# 2_classyTKL_SI_matrix.net
KiCad netlist of a schematic drawn in Altium Designer
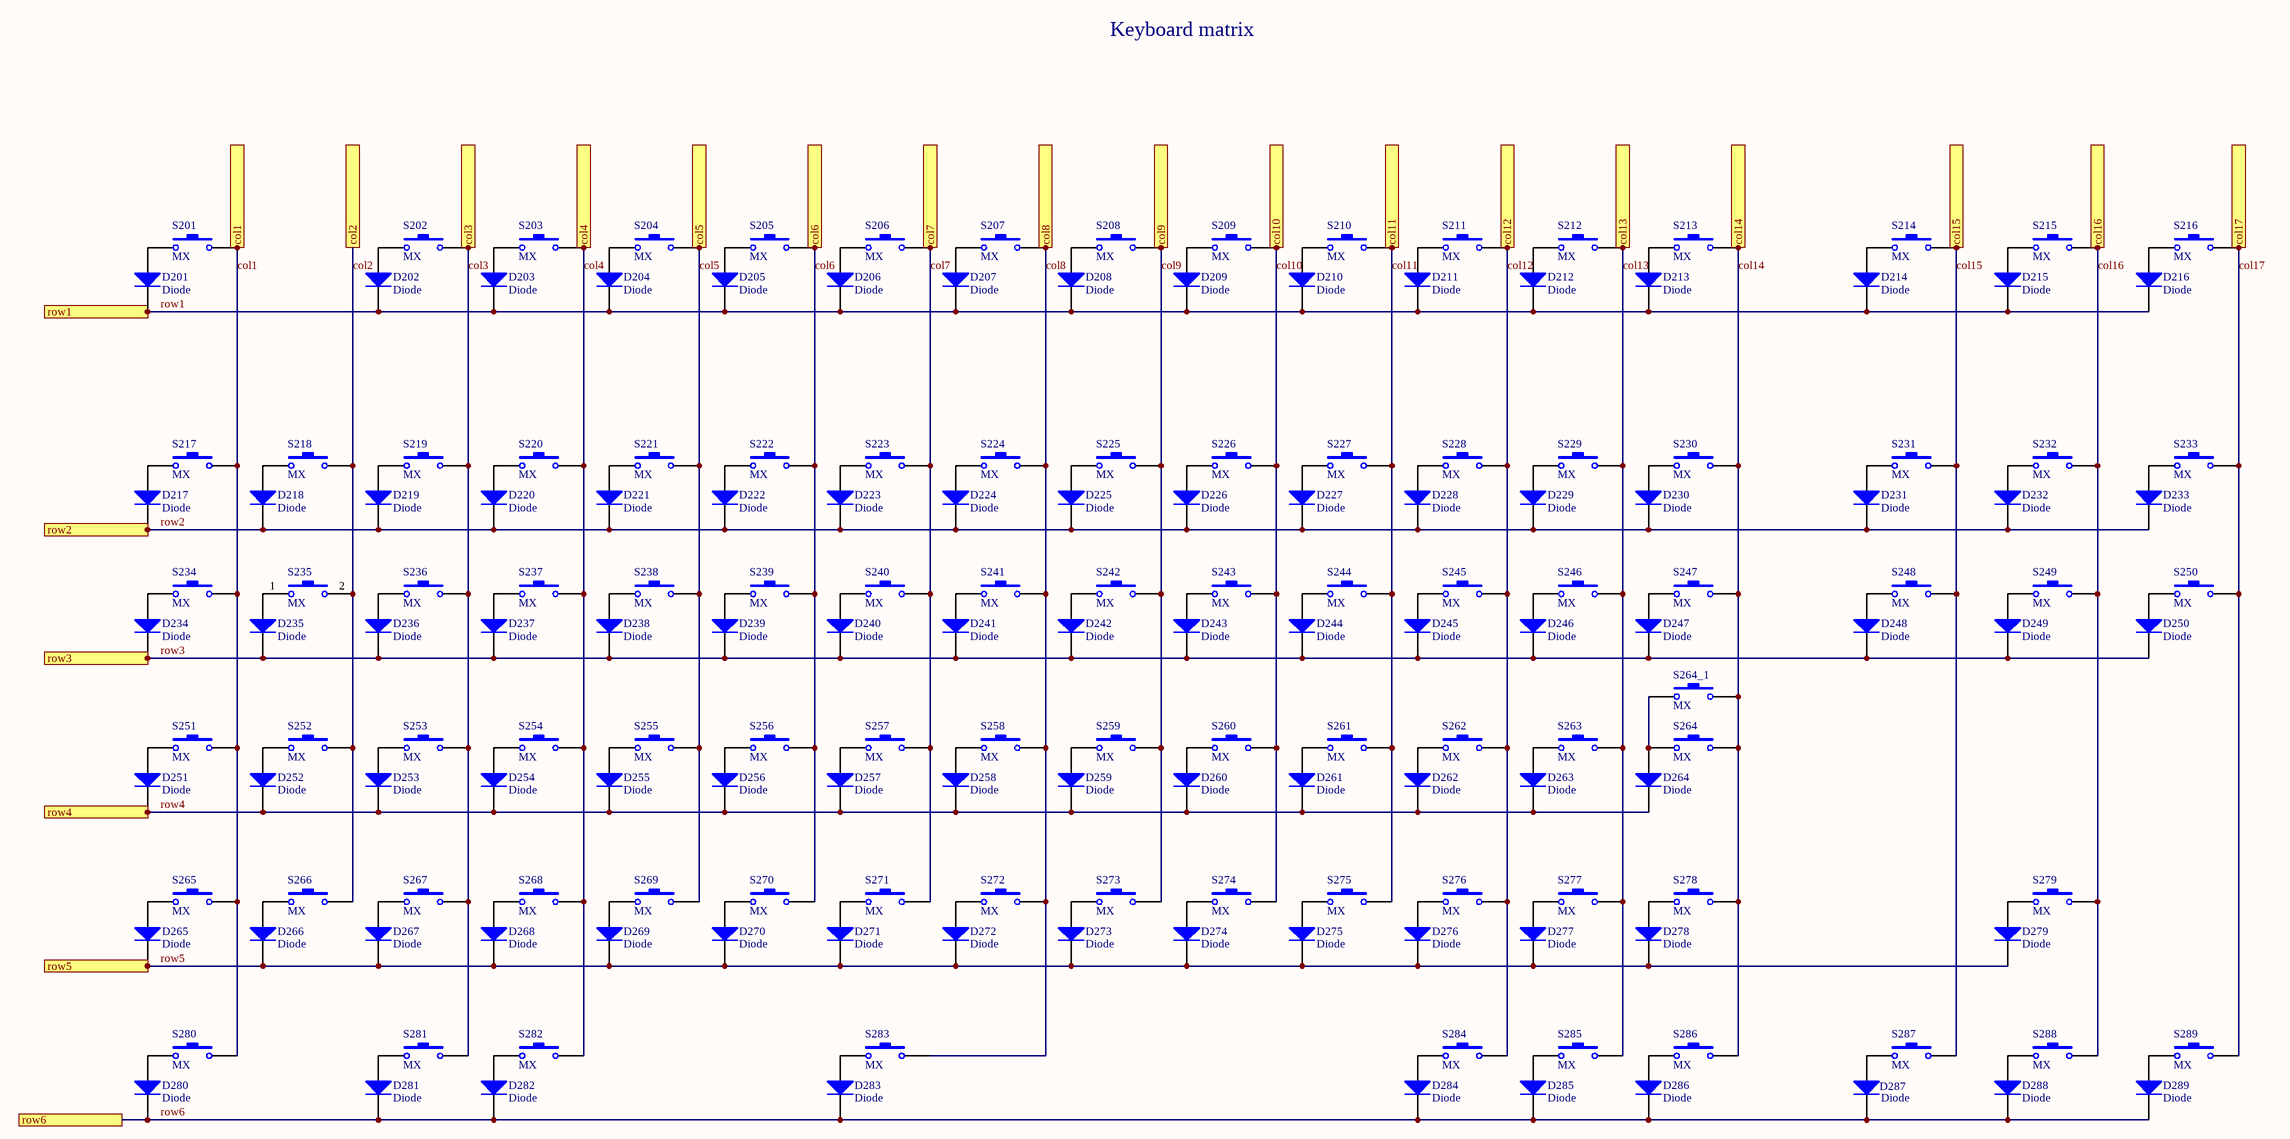
[diagram p0: 2_classyTKL_SI_matrix.SchDoc]

(export (version "E")
  (design (tool "Eeschema 10.0.6"))
  (components
    (comp (ref "D201")
      (value "Diode")
      (footprint "SOD-123")
      (description "Default Diode")
      (fields (field (name "LCSC PART #") "C81598") (field (name "MRF.PART") "1N4148W"))
      (libsource (lib "Miscellaneous Devices") (part "Diode"))
    )
    (comp (ref "D202")
      (value "Diode")
      (footprint "SOD-123")
      (description "Default Diode")
      (fields (field (name "LCSC PART #") "C81598") (field (name "MRF.PART") "1N4148W"))
      (libsource (lib "Miscellaneous Devices") (part "Diode"))
    )
    (comp (ref "D203")
      (value "Diode")
      (footprint "SOD-123")
      (description "Default Diode")
      (fields (field (name "LCSC PART #") "C81598") (field (name "MRF.PART") "1N4148W"))
      (libsource (lib "Miscellaneous Devices") (part "Diode"))
    )
    (comp (ref "D204")
      (value "Diode")
      (footprint "SOD-123")
      (description "Default Diode")
      (fields (field (name "LCSC PART #") "C81598") (field (name "MRF.PART") "1N4148W"))
      (libsource (lib "Miscellaneous Devices") (part "Diode"))
    )
    (comp (ref "D205")
      (value "Diode")
      (footprint "SOD-123")
      (description "Default Diode")
      (fields (field (name "LCSC PART #") "C81598") (field (name "MRF.PART") "1N4148W"))
      (libsource (lib "Miscellaneous Devices") (part "Diode"))
    )
    (comp (ref "D206")
      (value "Diode")
      (footprint "SOD-123")
      (description "Default Diode")
      (fields (field (name "LCSC PART #") "C81598") (field (name "MRF.PART") "1N4148W"))
      (libsource (lib "Miscellaneous Devices") (part "Diode"))
    )
    (comp (ref "D207")
      (value "Diode")
      (footprint "SOD-123")
      (description "Default Diode")
      (fields (field (name "LCSC PART #") "C81598") (field (name "MRF.PART") "1N4148W"))
      (libsource (lib "Miscellaneous Devices") (part "Diode"))
    )
    (comp (ref "D208")
      (value "Diode")
      (footprint "SOD-123")
      (description "Default Diode")
      (fields (field (name "LCSC PART #") "C81598") (field (name "MRF.PART") "1N4148W"))
      (libsource (lib "Miscellaneous Devices") (part "Diode"))
    )
    (comp (ref "D209")
      (value "Diode")
      (footprint "SOD-123")
      (description "Default Diode")
      (fields (field (name "LCSC PART #") "C81598") (field (name "MRF.PART") "1N4148W"))
      (libsource (lib "Miscellaneous Devices") (part "Diode"))
    )
    (comp (ref "D210")
      (value "Diode")
      (footprint "SOD-123")
      (description "Default Diode")
      (fields (field (name "LCSC PART #") "C81598") (field (name "MRF.PART") "1N4148W"))
      (libsource (lib "Miscellaneous Devices") (part "Diode"))
    )
    (comp (ref "D211")
      (value "Diode")
      (footprint "SOD-123")
      (description "Default Diode")
      (fields (field (name "LCSC PART #") "C81598") (field (name "MRF.PART") "1N4148W"))
      (libsource (lib "Miscellaneous Devices") (part "Diode"))
    )
    (comp (ref "D212")
      (value "Diode")
      (footprint "SOD-123")
      (description "Default Diode")
      (fields (field (name "LCSC PART #") "C81598") (field (name "MRF.PART") "1N4148W"))
      (libsource (lib "Miscellaneous Devices") (part "Diode"))
    )
    (comp (ref "D213")
      (value "Diode")
      (footprint "SOD-123")
      (description "Default Diode")
      (fields (field (name "LCSC PART #") "C81598") (field (name "MRF.PART") "1N4148W"))
      (libsource (lib "Miscellaneous Devices") (part "Diode"))
    )
    (comp (ref "D214")
      (value "Diode")
      (footprint "SOD-123")
      (description "Default Diode")
      (fields (field (name "LCSC PART #") "C81598") (field (name "MRF.PART") "1N4148W"))
      (libsource (lib "Miscellaneous Devices") (part "Diode"))
    )
    (comp (ref "D215")
      (value "Diode")
      (footprint "SOD-123")
      (description "Default Diode")
      (fields (field (name "LCSC PART #") "C81598") (field (name "MRF.PART") "1N4148W"))
      (libsource (lib "Miscellaneous Devices") (part "Diode"))
    )
    (comp (ref "D216")
      (value "Diode")
      (footprint "SOD-123")
      (description "Default Diode")
      (fields (field (name "LCSC PART #") "C81598") (field (name "MRF.PART") "1N4148W"))
      (libsource (lib "Miscellaneous Devices") (part "Diode"))
    )
    (comp (ref "D217")
      (value "Diode")
      (footprint "SOD-123")
      (description "Default Diode")
      (fields (field (name "LCSC PART #") "C81598") (field (name "MRF.PART") "1N4148W"))
      (libsource (lib "Miscellaneous Devices") (part "Diode"))
    )
    (comp (ref "D218")
      (value "Diode")
      (footprint "SOD-123")
      (description "Default Diode")
      (fields (field (name "LCSC PART #") "C81598") (field (name "MRF.PART") "1N4148W"))
      (libsource (lib "Miscellaneous Devices") (part "Diode"))
    )
    (comp (ref "D219")
      (value "Diode")
      (footprint "SOD-123")
      (description "Default Diode")
      (fields (field (name "LCSC PART #") "C81598") (field (name "MRF.PART") "1N4148W"))
      (libsource (lib "Miscellaneous Devices") (part "Diode"))
    )
    (comp (ref "D220")
      (value "Diode")
      (footprint "SOD-123")
      (description "Default Diode")
      (fields (field (name "LCSC PART #") "C81598") (field (name "MRF.PART") "1N4148W"))
      (libsource (lib "Miscellaneous Devices") (part "Diode"))
    )
    (comp (ref "D221")
      (value "Diode")
      (footprint "SOD-123")
      (description "Default Diode")
      (fields (field (name "LCSC PART #") "C81598") (field (name "MRF.PART") "1N4148W"))
      (libsource (lib "Miscellaneous Devices") (part "Diode"))
    )
    (comp (ref "D222")
      (value "Diode")
      (footprint "SOD-123")
      (description "Default Diode")
      (fields (field (name "LCSC PART #") "C81598") (field (name "MRF.PART") "1N4148W"))
      (libsource (lib "Miscellaneous Devices") (part "Diode"))
    )
    (comp (ref "D223")
      (value "Diode")
      (footprint "SOD-123")
      (description "Default Diode")
      (fields (field (name "LCSC PART #") "C81598") (field (name "MRF.PART") "1N4148W"))
      (libsource (lib "Miscellaneous Devices") (part "Diode"))
    )
    (comp (ref "D224")
      (value "Diode")
      (footprint "SOD-123")
      (description "Default Diode")
      (fields (field (name "LCSC PART #") "C81598") (field (name "MRF.PART") "1N4148W"))
      (libsource (lib "Miscellaneous Devices") (part "Diode"))
    )
    (comp (ref "D225")
      (value "Diode")
      (footprint "SOD-123")
      (description "Default Diode")
      (fields (field (name "LCSC PART #") "C81598") (field (name "MRF.PART") "1N4148W"))
      (libsource (lib "Miscellaneous Devices") (part "Diode"))
    )
    (comp (ref "D226")
      (value "Diode")
      (footprint "SOD-123")
      (description "Default Diode")
      (fields (field (name "LCSC PART #") "C81598") (field (name "MRF.PART") "1N4148W"))
      (libsource (lib "Miscellaneous Devices") (part "Diode"))
    )
    (comp (ref "D227")
      (value "Diode")
      (footprint "SOD-123")
      (description "Default Diode")
      (fields (field (name "LCSC PART #") "C81598") (field (name "MRF.PART") "1N4148W"))
      (libsource (lib "Miscellaneous Devices") (part "Diode"))
    )
    (comp (ref "D228")
      (value "Diode")
      (footprint "SOD-123")
      (description "Default Diode")
      (fields (field (name "LCSC PART #") "C81598") (field (name "MRF.PART") "1N4148W"))
      (libsource (lib "Miscellaneous Devices") (part "Diode"))
    )
    (comp (ref "D229")
      (value "Diode")
      (footprint "SOD-123")
      (description "Default Diode")
      (fields (field (name "LCSC PART #") "C81598") (field (name "MRF.PART") "1N4148W"))
      (libsource (lib "Miscellaneous Devices") (part "Diode"))
    )
    (comp (ref "D230")
      (value "Diode")
      (footprint "SOD-123")
      (description "Default Diode")
      (fields (field (name "LCSC PART #") "C81598") (field (name "MRF.PART") "1N4148W"))
      (libsource (lib "Miscellaneous Devices") (part "Diode"))
    )
    (comp (ref "D231")
      (value "Diode")
      (footprint "SOD-123")
      (description "Default Diode")
      (fields (field (name "LCSC PART #") "C81598") (field (name "MRF.PART") "1N4148W"))
      (libsource (lib "Miscellaneous Devices") (part "Diode"))
    )
    (comp (ref "D232")
      (value "Diode")
      (footprint "SOD-123")
      (description "Default Diode")
      (fields (field (name "LCSC PART #") "C81598") (field (name "MRF.PART") "1N4148W"))
      (libsource (lib "Miscellaneous Devices") (part "Diode"))
    )
    (comp (ref "D233")
      (value "Diode")
      (footprint "SOD-123")
      (description "Default Diode")
      (fields (field (name "LCSC PART #") "C81598") (field (name "MRF.PART") "1N4148W"))
      (libsource (lib "Miscellaneous Devices") (part "Diode"))
    )
    (comp (ref "D234")
      (value "Diode")
      (footprint "SOD-123")
      (description "Default Diode")
      (fields (field (name "LCSC PART #") "C81598") (field (name "MRF.PART") "1N4148W"))
      (libsource (lib "Miscellaneous Devices") (part "Diode"))
    )
    (comp (ref "D235")
      (value "Diode")
      (footprint "SOD-123")
      (description "Default Diode")
      (fields (field (name "LCSC PART #") "C81598") (field (name "MRF.PART") "1N4148W"))
      (libsource (lib "Miscellaneous Devices") (part "Diode"))
    )
    (comp (ref "D236")
      (value "Diode")
      (footprint "SOD-123")
      (description "Default Diode")
      (fields (field (name "LCSC PART #") "C81598") (field (name "MRF.PART") "1N4148W"))
      (libsource (lib "Miscellaneous Devices") (part "Diode"))
    )
    (comp (ref "D237")
      (value "Diode")
      (footprint "SOD-123")
      (description "Default Diode")
      (fields (field (name "LCSC PART #") "C81598") (field (name "MRF.PART") "1N4148W"))
      (libsource (lib "Miscellaneous Devices") (part "Diode"))
    )
    (comp (ref "D238")
      (value "Diode")
      (footprint "SOD-123")
      (description "Default Diode")
      (fields (field (name "LCSC PART #") "C81598") (field (name "MRF.PART") "1N4148W"))
      (libsource (lib "Miscellaneous Devices") (part "Diode"))
    )
    (comp (ref "D239")
      (value "Diode")
      (footprint "SOD-123")
      (description "Default Diode")
      (fields (field (name "LCSC PART #") "C81598") (field (name "MRF.PART") "1N4148W"))
      (libsource (lib "Miscellaneous Devices") (part "Diode"))
    )
    (comp (ref "D240")
      (value "Diode")
      (footprint "SOD-123")
      (description "Default Diode")
      (fields (field (name "LCSC PART #") "C81598") (field (name "MRF.PART") "1N4148W"))
      (libsource (lib "Miscellaneous Devices") (part "Diode"))
    )
    (comp (ref "D241")
      (value "Diode")
      (footprint "SOD-123")
      (description "Default Diode")
      (fields (field (name "LCSC PART #") "C81598") (field (name "MRF.PART") "1N4148W"))
      (libsource (lib "Miscellaneous Devices") (part "Diode"))
    )
    (comp (ref "D242")
      (value "Diode")
      (footprint "SOD-123")
      (description "Default Diode")
      (fields (field (name "LCSC PART #") "C81598") (field (name "MRF.PART") "1N4148W"))
      (libsource (lib "Miscellaneous Devices") (part "Diode"))
    )
    (comp (ref "D243")
      (value "Diode")
      (footprint "SOD-123")
      (description "Default Diode")
      (fields (field (name "LCSC PART #") "C81598") (field (name "MRF.PART") "1N4148W"))
      (libsource (lib "Miscellaneous Devices") (part "Diode"))
    )
    (comp (ref "D244")
      (value "Diode")
      (footprint "SOD-123")
      (description "Default Diode")
      (fields (field (name "LCSC PART #") "C81598") (field (name "MRF.PART") "1N4148W"))
      (libsource (lib "Miscellaneous Devices") (part "Diode"))
    )
    (comp (ref "D245")
      (value "Diode")
      (footprint "SOD-123")
      (description "Default Diode")
      (fields (field (name "LCSC PART #") "C81598") (field (name "MRF.PART") "1N4148W"))
      (libsource (lib "Miscellaneous Devices") (part "Diode"))
    )
    (comp (ref "D246")
      (value "Diode")
      (footprint "SOD-123")
      (description "Default Diode")
      (fields (field (name "LCSC PART #") "C81598") (field (name "MRF.PART") "1N4148W"))
      (libsource (lib "Miscellaneous Devices") (part "Diode"))
    )
    (comp (ref "D247")
      (value "Diode")
      (footprint "SOD-123")
      (description "Default Diode")
      (fields (field (name "LCSC PART #") "C81598") (field (name "MRF.PART") "1N4148W"))
      (libsource (lib "Miscellaneous Devices") (part "Diode"))
    )
    (comp (ref "D248")
      (value "Diode")
      (footprint "SOD-123")
      (description "Default Diode")
      (fields (field (name "LCSC PART #") "C81598") (field (name "MRF.PART") "1N4148W"))
      (libsource (lib "Miscellaneous Devices") (part "Diode"))
    )
    (comp (ref "D249")
      (value "Diode")
      (footprint "SOD-123")
      (description "Default Diode")
      (fields (field (name "LCSC PART #") "C81598") (field (name "MRF.PART") "1N4148W"))
      (libsource (lib "Miscellaneous Devices") (part "Diode"))
    )
    (comp (ref "D250")
      (value "Diode")
      (footprint "SOD-123")
      (description "Default Diode")
      (fields (field (name "LCSC PART #") "C81598") (field (name "MRF.PART") "1N4148W"))
      (libsource (lib "Miscellaneous Devices") (part "Diode"))
    )
    (comp (ref "D251")
      (value "Diode")
      (footprint "SOD-123")
      (description "Default Diode")
      (fields (field (name "LCSC PART #") "C81598") (field (name "MRF.PART") "1N4148W"))
      (libsource (lib "Miscellaneous Devices") (part "Diode"))
    )
    (comp (ref "D252")
      (value "Diode")
      (footprint "SOD-123")
      (description "Default Diode")
      (fields (field (name "LCSC PART #") "C81598") (field (name "MRF.PART") "1N4148W"))
      (libsource (lib "Miscellaneous Devices") (part "Diode"))
    )
    (comp (ref "D253")
      (value "Diode")
      (footprint "SOD-123")
      (description "Default Diode")
      (fields (field (name "LCSC PART #") "C81598") (field (name "MRF.PART") "1N4148W"))
      (libsource (lib "Miscellaneous Devices") (part "Diode"))
    )
    (comp (ref "D254")
      (value "Diode")
      (footprint "SOD-123")
      (description "Default Diode")
      (fields (field (name "LCSC PART #") "C81598") (field (name "MRF.PART") "1N4148W"))
      (libsource (lib "Miscellaneous Devices") (part "Diode"))
    )
    (comp (ref "D255")
      (value "Diode")
      (footprint "SOD-123")
      (description "Default Diode")
      (fields (field (name "LCSC PART #") "C81598") (field (name "MRF.PART") "1N4148W"))
      (libsource (lib "Miscellaneous Devices") (part "Diode"))
    )
    (comp (ref "D256")
      (value "Diode")
      (footprint "SOD-123")
      (description "Default Diode")
      (fields (field (name "LCSC PART #") "C81598") (field (name "MRF.PART") "1N4148W"))
      (libsource (lib "Miscellaneous Devices") (part "Diode"))
    )
    (comp (ref "D257")
      (value "Diode")
      (footprint "SOD-123")
      (description "Default Diode")
      (fields (field (name "LCSC PART #") "C81598") (field (name "MRF.PART") "1N4148W"))
      (libsource (lib "Miscellaneous Devices") (part "Diode"))
    )
    (comp (ref "D258")
      (value "Diode")
      (footprint "SOD-123")
      (description "Default Diode")
      (fields (field (name "LCSC PART #") "C81598") (field (name "MRF.PART") "1N4148W"))
      (libsource (lib "Miscellaneous Devices") (part "Diode"))
    )
    (comp (ref "D259")
      (value "Diode")
      (footprint "SOD-123")
      (description "Default Diode")
      (fields (field (name "LCSC PART #") "C81598") (field (name "MRF.PART") "1N4148W"))
      (libsource (lib "Miscellaneous Devices") (part "Diode"))
    )
    (comp (ref "D260")
      (value "Diode")
      (footprint "SOD-123")
      (description "Default Diode")
      (fields (field (name "LCSC PART #") "C81598") (field (name "MRF.PART") "1N4148W"))
      (libsource (lib "Miscellaneous Devices") (part "Diode"))
    )
    (comp (ref "D261")
      (value "Diode")
      (footprint "SOD-123")
      (description "Default Diode")
      (fields (field (name "LCSC PART #") "C81598") (field (name "MRF.PART") "1N4148W"))
      (libsource (lib "Miscellaneous Devices") (part "Diode"))
    )
    (comp (ref "D262")
      (value "Diode")
      (footprint "SOD-123")
      (description "Default Diode")
      (fields (field (name "LCSC PART #") "C81598") (field (name "MRF.PART") "1N4148W"))
      (libsource (lib "Miscellaneous Devices") (part "Diode"))
    )
    (comp (ref "D263")
      (value "Diode")
      (footprint "SOD-123")
      (description "Default Diode")
      (fields (field (name "LCSC PART #") "C81598") (field (name "MRF.PART") "1N4148W"))
      (libsource (lib "Miscellaneous Devices") (part "Diode"))
    )
    (comp (ref "D264")
      (value "Diode")
      (footprint "SOD-123")
      (description "Default Diode")
      (fields (field (name "LCSC PART #") "C81598") (field (name "MRF.PART") "1N4148W"))
      (libsource (lib "Miscellaneous Devices") (part "Diode"))
    )
    (comp (ref "D265")
      (value "Diode")
      (footprint "SOD-123")
      (description "Default Diode")
      (fields (field (name "LCSC PART #") "C81598") (field (name "MRF.PART") "1N4148W"))
      (libsource (lib "Miscellaneous Devices") (part "Diode"))
    )
    (comp (ref "D266")
      (value "Diode")
      (footprint "SOD-123")
      (description "Default Diode")
      (fields (field (name "LCSC PART #") "C81598") (field (name "MRF.PART") "1N4148W"))
      (libsource (lib "Miscellaneous Devices") (part "Diode"))
    )
    (comp (ref "D267")
      (value "Diode")
      (footprint "SOD-123")
      (description "Default Diode")
      (fields (field (name "LCSC PART #") "C81598") (field (name "MRF.PART") "1N4148W"))
      (libsource (lib "Miscellaneous Devices") (part "Diode"))
    )
    (comp (ref "D268")
      (value "Diode")
      (footprint "SOD-123")
      (description "Default Diode")
      (fields (field (name "LCSC PART #") "C81598") (field (name "MRF.PART") "1N4148W"))
      (libsource (lib "Miscellaneous Devices") (part "Diode"))
    )
    (comp (ref "D269")
      (value "Diode")
      (footprint "SOD-123")
      (description "Default Diode")
      (fields (field (name "LCSC PART #") "C81598") (field (name "MRF.PART") "1N4148W"))
      (libsource (lib "Miscellaneous Devices") (part "Diode"))
    )
    (comp (ref "D270")
      (value "Diode")
      (footprint "SOD-123")
      (description "Default Diode")
      (fields (field (name "LCSC PART #") "C81598") (field (name "MRF.PART") "1N4148W"))
      (libsource (lib "Miscellaneous Devices") (part "Diode"))
    )
    (comp (ref "D271")
      (value "Diode")
      (footprint "SOD-123")
      (description "Default Diode")
      (fields (field (name "LCSC PART #") "C81598") (field (name "MRF.PART") "1N4148W"))
      (libsource (lib "Miscellaneous Devices") (part "Diode"))
    )
    (comp (ref "D272")
      (value "Diode")
      (footprint "SOD-123")
      (description "Default Diode")
      (fields (field (name "LCSC PART #") "C81598") (field (name "MRF.PART") "1N4148W"))
      (libsource (lib "Miscellaneous Devices") (part "Diode"))
    )
    (comp (ref "D273")
      (value "Diode")
      (footprint "SOD-123")
      (description "Default Diode")
      (fields (field (name "LCSC PART #") "C81598") (field (name "MRF.PART") "1N4148W"))
      (libsource (lib "Miscellaneous Devices") (part "Diode"))
    )
    (comp (ref "D274")
      (value "Diode")
      (footprint "SOD-123")
      (description "Default Diode")
      (fields (field (name "LCSC PART #") "C81598") (field (name "MRF.PART") "1N4148W"))
      (libsource (lib "Miscellaneous Devices") (part "Diode"))
    )
    (comp (ref "D275")
      (value "Diode")
      (footprint "SOD-123")
      (description "Default Diode")
      (fields (field (name "LCSC PART #") "C81598") (field (name "MRF.PART") "1N4148W"))
      (libsource (lib "Miscellaneous Devices") (part "Diode"))
    )
    (comp (ref "D276")
      (value "Diode")
      (footprint "SOD-123")
      (description "Default Diode")
      (fields (field (name "LCSC PART #") "C81598") (field (name "MRF.PART") "1N4148W"))
      (libsource (lib "Miscellaneous Devices") (part "Diode"))
    )
    (comp (ref "D277")
      (value "Diode")
      (footprint "SOD-123")
      (description "Default Diode")
      (fields (field (name "LCSC PART #") "C81598") (field (name "MRF.PART") "1N4148W"))
      (libsource (lib "Miscellaneous Devices") (part "Diode"))
    )
    (comp (ref "D278")
      (value "Diode")
      (footprint "SOD-123")
      (description "Default Diode")
      (fields (field (name "LCSC PART #") "C81598") (field (name "MRF.PART") "1N4148W"))
      (libsource (lib "Miscellaneous Devices") (part "Diode"))
    )
    (comp (ref "D279")
      (value "Diode")
      (footprint "SOD-123")
      (description "Default Diode")
      (fields (field (name "LCSC PART #") "C81598") (field (name "MRF.PART") "1N4148W"))
      (libsource (lib "Miscellaneous Devices") (part "Diode"))
    )
    (comp (ref "D280")
      (value "Diode")
      (footprint "SOD-123")
      (description "Default Diode")
      (fields (field (name "LCSC PART #") "C81598") (field (name "MRF.PART") "1N4148W"))
      (libsource (lib "Miscellaneous Devices") (part "Diode"))
    )
    (comp (ref "D281")
      (value "Diode")
      (footprint "SOD-123")
      (description "Default Diode")
      (fields (field (name "LCSC PART #") "C81598") (field (name "MRF.PART") "1N4148W"))
      (libsource (lib "Miscellaneous Devices") (part "Diode"))
    )
    (comp (ref "D282")
      (value "Diode")
      (footprint "SOD-123")
      (description "Default Diode")
      (fields (field (name "LCSC PART #") "C81598") (field (name "MRF.PART") "1N4148W"))
      (libsource (lib "Miscellaneous Devices") (part "Diode"))
    )
    (comp (ref "D283")
      (value "Diode")
      (footprint "SOD-123")
      (description "Default Diode")
      (fields (field (name "LCSC PART #") "C81598") (field (name "MRF.PART") "1N4148W"))
      (libsource (lib "Miscellaneous Devices") (part "Diode"))
    )
    (comp (ref "D284")
      (value "Diode")
      (footprint "SOD-123")
      (description "Default Diode")
      (fields (field (name "LCSC PART #") "C81598") (field (name "MRF.PART") "1N4148W"))
      (libsource (lib "Miscellaneous Devices") (part "Diode"))
    )
    (comp (ref "D285")
      (value "Diode")
      (footprint "SOD-123")
      (description "Default Diode")
      (fields (field (name "LCSC PART #") "C81598") (field (name "MRF.PART") "1N4148W"))
      (libsource (lib "Miscellaneous Devices") (part "Diode"))
    )
    (comp (ref "D286")
      (value "Diode")
      (footprint "SOD-123")
      (description "Default Diode")
      (fields (field (name "LCSC PART #") "C81598") (field (name "MRF.PART") "1N4148W"))
      (libsource (lib "Miscellaneous Devices") (part "Diode"))
    )
    (comp (ref "D287")
      (value "Diode")
      (footprint "SOD-123")
      (description "Default Diode")
      (fields (field (name "LCSC PART #") "C81598") (field (name "MRF.PART") "1N4148W"))
      (libsource (lib "Miscellaneous Devices") (part "Diode"))
    )
    (comp (ref "D288")
      (value "Diode")
      (footprint "SOD-123")
      (description "Default Diode")
      (fields (field (name "LCSC PART #") "C81598") (field (name "MRF.PART") "1N4148W"))
      (libsource (lib "Miscellaneous Devices") (part "Diode"))
    )
    (comp (ref "D289")
      (value "Diode")
      (footprint "SOD-123")
      (description "Default Diode")
      (fields (field (name "LCSC PART #") "C81598") (field (name "MRF.PART") "1N4148W"))
      (libsource (lib "Miscellaneous Devices") (part "Diode"))
    )
    (comp (ref "S201")
      (value "MX")
      (footprint "NMB-Switch 1U - switched pol  - no allignment pins")
      (description "Switch")
      (libsource (lib "Miscellaneous Devices") (part "SW-PB"))
    )
    (comp (ref "S202")
      (value "MX")
      (footprint "NMB-Switch 1U - no allignment pins")
      (description "Switch")
      (libsource (lib "Miscellaneous Devices") (part "SW-PB"))
    )
    (comp (ref "S203")
      (value "MX")
      (footprint "NMB-Switch 1U - no allignment pins")
      (description "Switch")
      (libsource (lib "Miscellaneous Devices") (part "SW-PB"))
    )
    (comp (ref "S204")
      (value "MX")
      (footprint "NMB-Switch 1U - no allignment pins")
      (description "Switch")
      (libsource (lib "Miscellaneous Devices") (part "SW-PB"))
    )
    (comp (ref "S205")
      (value "MX")
      (footprint "NMB-Switch 1U - switched pol  - no allignment pins")
      (description "Switch")
      (libsource (lib "Miscellaneous Devices") (part "SW-PB"))
    )
    (comp (ref "S206")
      (value "MX")
      (footprint "NMB-Switch 1U - no allignment pins")
      (description "Switch")
      (libsource (lib "Miscellaneous Devices") (part "SW-PB"))
    )
    (comp (ref "S207")
      (value "MX")
      (footprint "NMB-Switch 1U - no allignment pins")
      (description "Switch")
      (libsource (lib "Miscellaneous Devices") (part "SW-PB"))
    )
    (comp (ref "S208")
      (value "MX")
      (footprint "NMB-Switch 1U - no allignment pins")
      (description "Switch")
      (libsource (lib "Miscellaneous Devices") (part "SW-PB"))
    )
    (comp (ref "S209")
      (value "MX")
      (footprint "NMB-Switch 1U - no allignment pins")
      (description "Switch")
      (libsource (lib "Miscellaneous Devices") (part "SW-PB"))
    )
    (comp (ref "S210")
      (value "MX")
      (footprint "NMB-Switch 1U - no allignment pins")
      (description "Switch")
      (libsource (lib "Miscellaneous Devices") (part "SW-PB"))
    )
    (comp (ref "S211")
      (value "MX")
      (footprint "NMB-Switch 1U - no allignment pins")
      (description "Switch")
      (libsource (lib "Miscellaneous Devices") (part "SW-PB"))
    )
    (comp (ref "S212")
      (value "MX")
      (footprint "NMB-Switch 1U - no allignment pins")
      (description "Switch")
      (libsource (lib "Miscellaneous Devices") (part "SW-PB"))
    )
    (comp (ref "S213")
      (value "MX")
      (footprint "NMB-Switch 1U - no allignment pins")
      (description "Switch")
      (libsource (lib "Miscellaneous Devices") (part "SW-PB"))
    )
    (comp (ref "S214")
      (value "MX")
      (footprint "NMB-Switch 1U - no allignment pins")
      (description "Switch")
      (libsource (lib "Miscellaneous Devices") (part "SW-PB"))
    )
    (comp (ref "S215")
      (value "MX")
      (footprint "NMB-Switch 1U - no allignment pins")
      (description "Switch")
      (libsource (lib "Miscellaneous Devices") (part "SW-PB"))
    )
    (comp (ref "S216")
      (value "MX")
      (footprint "NMB-Switch 1U - no allignment pins")
      (description "Switch")
      (libsource (lib "Miscellaneous Devices") (part "SW-PB"))
    )
    (comp (ref "S217")
      (value "MX")
      (footprint "NMB-Switch 1U - switched pol  - no allignment pins")
      (description "Switch")
      (libsource (lib "Miscellaneous Devices") (part "SW-PB"))
    )
    (comp (ref "S218")
      (value "MX")
      (footprint "NMB-Switch 1U - switched pol  - no allignment pins")
      (description "Switch")
      (libsource (lib "Miscellaneous Devices") (part "SW-PB"))
    )
    (comp (ref "S219")
      (value "MX")
      (footprint "NMB-Switch 1U - switched pol  - no allignment pins")
      (description "Switch")
      (libsource (lib "Miscellaneous Devices") (part "SW-PB"))
    )
    (comp (ref "S220")
      (value "MX")
      (footprint "NMB-Switch 1U - switched pol  - no allignment pins")
      (description "Switch")
      (libsource (lib "Miscellaneous Devices") (part "SW-PB"))
    )
    (comp (ref "S221")
      (value "MX")
      (footprint "NMB-Switch 1U - switched pol  - no allignment pins")
      (description "Switch")
      (libsource (lib "Miscellaneous Devices") (part "SW-PB"))
    )
    (comp (ref "S222")
      (value "MX")
      (footprint "NMB-Switch 1U - switched pol  - no allignment pins")
      (description "Switch")
      (libsource (lib "Miscellaneous Devices") (part "SW-PB"))
    )
    (comp (ref "S223")
      (value "MX")
      (footprint "NMB-Switch 1U - switched pol  - no allignment pins")
      (description "Switch")
      (libsource (lib "Miscellaneous Devices") (part "SW-PB"))
    )
    (comp (ref "S224")
      (value "MX")
      (footprint "NMB-Switch 1U - switched pol  - no allignment pins")
      (description "Switch")
      (libsource (lib "Miscellaneous Devices") (part "SW-PB"))
    )
    (comp (ref "S225")
      (value "MX")
      (footprint "NMB-Switch 1U - switched pol  - no allignment pins")
      (description "Switch")
      (libsource (lib "Miscellaneous Devices") (part "SW-PB"))
    )
    (comp (ref "S226")
      (value "MX")
      (footprint "NMB-Switch 1U - switched pol  - no allignment pins")
      (description "Switch")
      (libsource (lib "Miscellaneous Devices") (part "SW-PB"))
    )
    (comp (ref "S227")
      (value "MX")
      (footprint "NMB-Switch 1U - switched pol  - no allignment pins")
      (description "Switch")
      (libsource (lib "Miscellaneous Devices") (part "SW-PB"))
    )
    (comp (ref "S228")
      (value "MX")
      (footprint "NMB-Switch 1U - switched pol  - no allignment pins")
      (description "Switch")
      (libsource (lib "Miscellaneous Devices") (part "SW-PB"))
    )
    (comp (ref "S229")
      (value "MX")
      (footprint "NMB-Switch 1U - switched pol  - no allignment pins")
      (description "Switch")
      (libsource (lib "Miscellaneous Devices") (part "SW-PB"))
    )
    (comp (ref "S230")
      (value "MX")
      (footprint "NMB-Switch 1U - no allignment pins")
      (description "Switch")
      (libsource (lib "Miscellaneous Devices") (part "SW-PB"))
    )
    (comp (ref "S231")
      (value "MX")
      (footprint "NMB-Switch 1U - no allignment pins")
      (description "Switch")
      (libsource (lib "Miscellaneous Devices") (part "SW-PB"))
    )
    (comp (ref "S232")
      (value "MX")
      (footprint "NMB-Switch 1U - no allignment pins")
      (description "Switch")
      (libsource (lib "Miscellaneous Devices") (part "SW-PB"))
    )
    (comp (ref "S233")
      (value "MX")
      (footprint "NMB-Switch 1U - no allignment pins")
      (description "Switch")
      (libsource (lib "Miscellaneous Devices") (part "SW-PB"))
    )
    (comp (ref "S234")
      (value "MX")
      (footprint "NMB-Switch 1U - switched pol  - no allignment pins")
      (description "TAB")
      (libsource (lib "Miscellaneous Devices") (part "SW-PB"))
    )
    (comp (ref "S235")
      (value "MX")
      (footprint "NMB-Switch 1U - switched pol  - no allignment pins")
      (description "Switch")
      (libsource (lib "") (part "SW-PB_1"))
    )
    (comp (ref "S236")
      (value "MX")
      (footprint "NMB-Switch 1U - switched pol  - no allignment pins")
      (description "Switch")
      (libsource (lib "Miscellaneous Devices") (part "SW-PB"))
    )
    (comp (ref "S237")
      (value "MX")
      (footprint "NMB-Switch 1U - switched pol  - no allignment pins")
      (description "Switch")
      (libsource (lib "Miscellaneous Devices") (part "SW-PB"))
    )
    (comp (ref "S238")
      (value "MX")
      (footprint "NMB-Switch 1U - switched pol  - no allignment pins")
      (description "Switch")
      (libsource (lib "Miscellaneous Devices") (part "SW-PB"))
    )
    (comp (ref "S239")
      (value "MX")
      (footprint "NMB-Switch 1U - switched pol  - no allignment pins")
      (description "Switch")
      (libsource (lib "Miscellaneous Devices") (part "SW-PB"))
    )
    (comp (ref "S240")
      (value "MX")
      (footprint "NMB-Switch 1U - switched pol  - no allignment pins")
      (description "Switch")
      (libsource (lib "Miscellaneous Devices") (part "SW-PB"))
    )
    (comp (ref "S241")
      (value "MX")
      (footprint "NMB-Switch 1U - switched pol  - no allignment pins")
      (description "Switch")
      (libsource (lib "Miscellaneous Devices") (part "SW-PB"))
    )
    (comp (ref "S242")
      (value "MX")
      (footprint "NMB-Switch 1U - switched pol  - no allignment pins")
      (description "Switch")
      (libsource (lib "Miscellaneous Devices") (part "SW-PB"))
    )
    (comp (ref "S243")
      (value "MX")
      (footprint "NMB-Switch 1U - switched pol  - no allignment pins")
      (description "Switch")
      (libsource (lib "Miscellaneous Devices") (part "SW-PB"))
    )
    (comp (ref "S244")
      (value "MX")
      (footprint "NMB-Switch 1U - switched pol  - no allignment pins")
      (description "Switch")
      (libsource (lib "Miscellaneous Devices") (part "SW-PB"))
    )
    (comp (ref "S245")
      (value "MX")
      (footprint "NMB-Switch 1U - switched pol  - no allignment pins")
      (description "Switch")
      (libsource (lib "Miscellaneous Devices") (part "SW-PB"))
    )
    (comp (ref "S246")
      (value "MX")
      (footprint "NMB-Switch 1U - switched pol  - no allignment pins")
      (description "Switch")
      (libsource (lib "Miscellaneous Devices") (part "SW-PB"))
    )
    (comp (ref "S247")
      (value "MX")
      (footprint "MX-switch - PIPE_ISO_ENTER")
      (description "Switch")
      (libsource (lib "Miscellaneous Devices") (part "SW-PB"))
    )
    (comp (ref "S248")
      (value "MX")
      (footprint "NMB-Switch 1U - no allignment pins")
      (description "Switch")
      (libsource (lib "Miscellaneous Devices") (part "SW-PB"))
    )
    (comp (ref "S249")
      (value "MX")
      (footprint "NMB-Switch 1U - no allignment pins")
      (description "Switch")
      (libsource (lib "Miscellaneous Devices") (part "SW-PB"))
    )
    (comp (ref "S250")
      (value "MX")
      (footprint "NMB-Switch 1U - no allignment pins")
      (description "Switch")
      (libsource (lib "Miscellaneous Devices") (part "SW-PB"))
    )
    (comp (ref "S251")
      (value "MX")
      (footprint "MX-switch - CAPS")
      (description "Switch")
      (libsource (lib "Miscellaneous Devices") (part "SW-PB"))
    )
    (comp (ref "S252")
      (value "MX")
      (footprint "NMB-Switch 1U - switched pol  - no allignment pins")
      (description "Switch")
      (libsource (lib "Miscellaneous Devices") (part "SW-PB"))
    )
    (comp (ref "S253")
      (value "MX")
      (footprint "NMB-Switch 1U - switched pol  - no allignment pins")
      (description "Switch")
      (libsource (lib "Miscellaneous Devices") (part "SW-PB"))
    )
    (comp (ref "S254")
      (value "MX")
      (footprint "NMB-Switch 1U - switched pol  - no allignment pins")
      (description "Switch")
      (libsource (lib "Miscellaneous Devices") (part "SW-PB"))
    )
    (comp (ref "S255")
      (value "MX")
      (footprint "NMB-Switch 1U - switched pol  - no allignment pins")
      (description "Switch")
      (libsource (lib "Miscellaneous Devices") (part "SW-PB"))
    )
    (comp (ref "S256")
      (value "MX")
      (footprint "NMB-Switch 1U - switched pol  - no allignment pins")
      (description "Switch")
      (libsource (lib "Miscellaneous Devices") (part "SW-PB"))
    )
    (comp (ref "S257")
      (value "MX")
      (footprint "NMB-Switch 1U - switched pol  - no allignment pins")
      (description "Switch")
      (libsource (lib "Miscellaneous Devices") (part "SW-PB"))
    )
    (comp (ref "S258")
      (value "MX")
      (footprint "NMB-Switch 1U - switched pol  - no allignment pins")
      (description "Switch")
      (libsource (lib "Miscellaneous Devices") (part "SW-PB"))
    )
    (comp (ref "S259")
      (value "MX")
      (footprint "NMB-Switch 1U - switched pol  - no allignment pins")
      (description "Switch")
      (libsource (lib "Miscellaneous Devices") (part "SW-PB"))
    )
    (comp (ref "S260")
      (value "MX")
      (footprint "NMB-Switch 1U - switched pol  - no allignment pins")
      (description "Switch")
      (libsource (lib "Miscellaneous Devices") (part "SW-PB"))
    )
    (comp (ref "S261")
      (value "MX")
      (footprint "NMB-Switch 1U - switched pol  - no allignment pins")
      (description "Switch")
      (libsource (lib "Miscellaneous Devices") (part "SW-PB"))
    )
    (comp (ref "S262")
      (value "MX")
      (footprint "NMB-Switch 1U - switched pol  - no allignment pins")
      (description "Switch")
      (libsource (lib "Miscellaneous Devices") (part "SW-PB"))
    )
    (comp (ref "S263")
      (value "MX")
      (footprint "MX-switch - Enter_ANSI_ISO_KEY")
      (description "Switch")
      (libsource (lib "Miscellaneous Devices") (part "SW-PB"))
    )
    (comp (ref "S264")
      (value "MX")
      (footprint "NMB-Switch 1U - switched pol  - no allignment pins")
      (description "Switch")
      (libsource (lib "Miscellaneous Devices") (part "SW-PB"))
    )
    (comp (ref "S264_1")
      (value "MX")
      (footprint "NMB-Switch 1U - no allignment pins")
      (description "Switch")
      (libsource (lib "Miscellaneous Devices") (part "SW-PB"))
    )
    (comp (ref "S265")
      (value "MX")
      (footprint "MX-switch - Left shift")
      (description "Switch")
      (libsource (lib "Miscellaneous Devices") (part "SW-PB"))
    )
    (comp (ref "S266")
      (value "MX")
      (footprint "NMB-Switch 1U - switched pol  - no allignment pins")
      (description "Switch")
      (libsource (lib "Miscellaneous Devices") (part "SW-PB"))
    )
    (comp (ref "S267")
      (value "MX")
      (footprint "NMB-Switch 1U - switched pol  - no allignment pins")
      (description "Switch")
      (libsource (lib "Miscellaneous Devices") (part "SW-PB"))
    )
    (comp (ref "S268")
      (value "MX")
      (footprint "NMB-Switch 1U - switched pol  - no allignment pins")
      (description "Switch")
      (libsource (lib "Miscellaneous Devices") (part "SW-PB"))
    )
    (comp (ref "S269")
      (value "MX")
      (footprint "NMB-Switch 1U - switched pol  - no allignment pins")
      (description "Switch")
      (libsource (lib "Miscellaneous Devices") (part "SW-PB"))
    )
    (comp (ref "S270")
      (value "MX")
      (footprint "NMB-Switch 1U - switched pol  - no allignment pins")
      (description "Switch")
      (libsource (lib "Miscellaneous Devices") (part "SW-PB"))
    )
    (comp (ref "S271")
      (value "MX")
      (footprint "NMB-Switch 1U - switched pol  - no allignment pins")
      (description "Switch")
      (libsource (lib "Miscellaneous Devices") (part "SW-PB"))
    )
    (comp (ref "S272")
      (value "MX")
      (footprint "NMB-Switch 1U - switched pol  - no allignment pins")
      (description "Switch")
      (libsource (lib "Miscellaneous Devices") (part "SW-PB"))
    )
    (comp (ref "S273")
      (value "MX")
      (footprint "NMB-Switch 1U - switched pol  - no allignment pins")
      (description "Switch")
      (libsource (lib "Miscellaneous Devices") (part "SW-PB"))
    )
    (comp (ref "S274")
      (value "MX")
      (footprint "NMB-Switch 1U - switched pol  - no allignment pins")
      (description "Switch")
      (libsource (lib "Miscellaneous Devices") (part "SW-PB"))
    )
    (comp (ref "S275")
      (value "MX")
      (footprint "NMB-Switch 1U - switched pol  - no allignment pins")
      (description "Switch")
      (libsource (lib "Miscellaneous Devices") (part "SW-PB"))
    )
    (comp (ref "S276")
      (value "MX")
      (footprint "NMB-Switch 1U - switched pol  - no allignment pins")
      (description "Switch")
      (libsource (lib "Miscellaneous Devices") (part "SW-PB"))
    )
    (comp (ref "S277")
      (value "MX")
      (footprint "MX-switch - right shift")
      (description "Switch")
      (libsource (lib "Miscellaneous Devices") (part "SW-PB"))
    )
    (comp (ref "S278")
      (value "MX")
      (footprint "NMB-Switch 1U - switched pol  - no allignment pins")
      (description "Switch")
      (libsource (lib "Miscellaneous Devices") (part "SW-PB"))
    )
    (comp (ref "S279")
      (value "MX")
      (footprint "NMB-Switch 1U - no allignment pins")
      (description "Switch")
      (libsource (lib "Miscellaneous Devices") (part "SW-PB"))
    )
    (comp (ref "S280")
      (value "MX")
      (footprint "NMB-Switch 1U - switched pol  - no allignment pins")
      (description "Switch")
      (libsource (lib "Miscellaneous Devices") (part "SW-PB"))
    )
    (comp (ref "S281")
      (value "MX")
      (footprint "NMB-Switch 1U - no allignment pins")
      (description "Switch")
      (libsource (lib "Miscellaneous Devices") (part "SW-PB"))
    )
    (comp (ref "S282")
      (value "MX")
      (footprint "NMB-Switch 1U - no allignment pins")
      (description "Switch")
      (libsource (lib "Miscellaneous Devices") (part "SW-PB"))
    )
    (comp (ref "S283")
      (value "MX")
      (footprint "NMB-Switch 1U - no allignment pins")
      (description "Switch")
      (libsource (lib "Miscellaneous Devices") (part "SW-PB"))
    )
    (comp (ref "S284")
      (value "MX")
      (footprint "NMB-Switch 1U - no allignment pins")
      (description "Switch")
      (libsource (lib "Miscellaneous Devices") (part "SW-PB"))
    )
    (comp (ref "S285")
      (value "MX")
      (footprint "NMB-Switch 1U - no allignment pins")
      (description "Switch")
      (libsource (lib "Miscellaneous Devices") (part "SW-PB"))
    )
    (comp (ref "S286")
      (value "MX")
      (footprint "NMB-Switch 1U - no allignment pins")
      (description "Switch")
      (libsource (lib "Miscellaneous Devices") (part "SW-PB"))
    )
    (comp (ref "S287")
      (value "MX")
      (footprint "NMB-Switch 1U - no allignment pins")
      (description "Switch")
      (libsource (lib "Miscellaneous Devices") (part "SW-PB"))
    )
    (comp (ref "S288")
      (value "MX")
      (footprint "NMB-Switch 1U - no allignment pins")
      (description "Switch")
      (libsource (lib "Miscellaneous Devices") (part "SW-PB"))
    )
    (comp (ref "S289")
      (value "MX")
      (footprint "NMB-Switch 1U - no allignment pins")
      (description "Switch")
      (libsource (lib "Miscellaneous Devices") (part "SW-PB"))
    )
  )
  (nets
    (net (code "1") (name "/col1") (class "Default")
      (node (ref "S201") (pin "2") (pinfunction "2_2") (pintype "passive"))
      (node (ref "S217") (pin "2") (pinfunction "2_2") (pintype "passive"))
      (node (ref "S234") (pin "2") (pinfunction "2_2") (pintype "passive"))
      (node (ref "S251") (pin "2") (pinfunction "2_2") (pintype "passive"))
      (node (ref "S265") (pin "2") (pinfunction "2_2") (pintype "passive"))
      (node (ref "S280") (pin "2") (pinfunction "2_2") (pintype "passive"))
    )
    (net (code "2") (name "/col2") (class "Default")
      (node (ref "S218") (pin "2") (pinfunction "2_2") (pintype "passive"))
      (node (ref "S235") (pin "2") (pinfunction "2_2") (pintype "passive"))
      (node (ref "S252") (pin "2") (pinfunction "2_2") (pintype "passive"))
      (node (ref "S266") (pin "2") (pinfunction "2_2") (pintype "passive"))
    )
    (net (code "3") (name "/col3") (class "Default")
      (node (ref "S202") (pin "2") (pinfunction "2_2") (pintype "passive"))
      (node (ref "S219") (pin "2") (pinfunction "2_2") (pintype "passive"))
      (node (ref "S236") (pin "2") (pinfunction "2_2") (pintype "passive"))
      (node (ref "S253") (pin "2") (pinfunction "2_2") (pintype "passive"))
      (node (ref "S267") (pin "2") (pinfunction "2_2") (pintype "passive"))
      (node (ref "S281") (pin "2") (pinfunction "2_2") (pintype "passive"))
    )
    (net (code "4") (name "/col4") (class "Default")
      (node (ref "S203") (pin "2") (pinfunction "2_2") (pintype "passive"))
      (node (ref "S220") (pin "2") (pinfunction "2_2") (pintype "passive"))
      (node (ref "S237") (pin "2") (pinfunction "2_2") (pintype "passive"))
      (node (ref "S254") (pin "2") (pinfunction "2_2") (pintype "passive"))
      (node (ref "S268") (pin "2") (pinfunction "2_2") (pintype "passive"))
      (node (ref "S282") (pin "2") (pinfunction "2_2") (pintype "passive"))
    )
    (net (code "5") (name "/col5") (class "Default")
      (node (ref "S204") (pin "2") (pinfunction "2_2") (pintype "passive"))
      (node (ref "S221") (pin "2") (pinfunction "2_2") (pintype "passive"))
      (node (ref "S238") (pin "2") (pinfunction "2_2") (pintype "passive"))
      (node (ref "S255") (pin "2") (pinfunction "2_2") (pintype "passive"))
      (node (ref "S269") (pin "2") (pinfunction "2_2") (pintype "passive"))
    )
    (net (code "6") (name "/col6") (class "Default")
      (node (ref "S205") (pin "2") (pinfunction "2_2") (pintype "passive"))
      (node (ref "S222") (pin "2") (pinfunction "2_2") (pintype "passive"))
      (node (ref "S239") (pin "2") (pinfunction "2_2") (pintype "passive"))
      (node (ref "S256") (pin "2") (pinfunction "2_2") (pintype "passive"))
      (node (ref "S270") (pin "2") (pinfunction "2_2") (pintype "passive"))
    )
    (net (code "7") (name "/col7") (class "Default")
      (node (ref "S206") (pin "2") (pinfunction "2_2") (pintype "passive"))
      (node (ref "S223") (pin "2") (pinfunction "2_2") (pintype "passive"))
      (node (ref "S240") (pin "2") (pinfunction "2_2") (pintype "passive"))
      (node (ref "S257") (pin "2") (pinfunction "2_2") (pintype "passive"))
      (node (ref "S271") (pin "2") (pinfunction "2_2") (pintype "passive"))
    )
    (net (code "8") (name "/col8") (class "Default")
      (node (ref "S207") (pin "2") (pinfunction "2_2") (pintype "passive"))
      (node (ref "S224") (pin "2") (pinfunction "2_2") (pintype "passive"))
      (node (ref "S241") (pin "2") (pinfunction "2_2") (pintype "passive"))
      (node (ref "S258") (pin "2") (pinfunction "2_2") (pintype "passive"))
      (node (ref "S272") (pin "2") (pinfunction "2_2") (pintype "passive"))
      (node (ref "S283") (pin "2") (pinfunction "2_2") (pintype "passive"))
    )
    (net (code "9") (name "/col9") (class "Default")
      (node (ref "S208") (pin "2") (pinfunction "2_2") (pintype "passive"))
      (node (ref "S225") (pin "2") (pinfunction "2_2") (pintype "passive"))
      (node (ref "S242") (pin "2") (pinfunction "2_2") (pintype "passive"))
      (node (ref "S259") (pin "2") (pinfunction "2_2") (pintype "passive"))
      (node (ref "S273") (pin "2") (pinfunction "2_2") (pintype "passive"))
    )
    (net (code "10") (name "/col10") (class "Default")
      (node (ref "S209") (pin "2") (pinfunction "2_2") (pintype "passive"))
      (node (ref "S226") (pin "2") (pinfunction "2_2") (pintype "passive"))
      (node (ref "S243") (pin "2") (pinfunction "2_2") (pintype "passive"))
      (node (ref "S260") (pin "2") (pinfunction "2_2") (pintype "passive"))
      (node (ref "S274") (pin "2") (pinfunction "2_2") (pintype "passive"))
    )
    (net (code "11") (name "/col11") (class "Default")
      (node (ref "S210") (pin "2") (pinfunction "2_2") (pintype "passive"))
      (node (ref "S227") (pin "2") (pinfunction "2_2") (pintype "passive"))
      (node (ref "S244") (pin "2") (pinfunction "2_2") (pintype "passive"))
      (node (ref "S261") (pin "2") (pinfunction "2_2") (pintype "passive"))
      (node (ref "S275") (pin "2") (pinfunction "2_2") (pintype "passive"))
    )
    (net (code "12") (name "/col12") (class "Default")
      (node (ref "S211") (pin "2") (pinfunction "2_2") (pintype "passive"))
      (node (ref "S228") (pin "2") (pinfunction "2_2") (pintype "passive"))
      (node (ref "S245") (pin "2") (pinfunction "2_2") (pintype "passive"))
      (node (ref "S262") (pin "2") (pinfunction "2_2") (pintype "passive"))
      (node (ref "S276") (pin "2") (pinfunction "2_2") (pintype "passive"))
      (node (ref "S284") (pin "2") (pinfunction "2_2") (pintype "passive"))
    )
    (net (code "13") (name "/col13") (class "Default")
      (node (ref "S212") (pin "2") (pinfunction "2_2") (pintype "passive"))
      (node (ref "S229") (pin "2") (pinfunction "2_2") (pintype "passive"))
      (node (ref "S246") (pin "2") (pinfunction "2_2") (pintype "passive"))
      (node (ref "S263") (pin "2") (pinfunction "2_2") (pintype "passive"))
      (node (ref "S277") (pin "2") (pinfunction "2_2") (pintype "passive"))
      (node (ref "S285") (pin "2") (pinfunction "2_2") (pintype "passive"))
    )
    (net (code "14") (name "/col14") (class "Default")
      (node (ref "S213") (pin "2") (pinfunction "2_2") (pintype "passive"))
      (node (ref "S230") (pin "2") (pinfunction "2_2") (pintype "passive"))
      (node (ref "S247") (pin "2") (pinfunction "2_2") (pintype "passive"))
      (node (ref "S264") (pin "2") (pinfunction "2_2") (pintype "passive"))
      (node (ref "S264_1") (pin "2") (pinfunction "2_2") (pintype "passive"))
      (node (ref "S278") (pin "2") (pinfunction "2_2") (pintype "passive"))
      (node (ref "S286") (pin "2") (pinfunction "2_2") (pintype "passive"))
    )
    (net (code "15") (name "/col15") (class "Default")
      (node (ref "S214") (pin "2") (pinfunction "2_2") (pintype "passive"))
      (node (ref "S231") (pin "2") (pinfunction "2_2") (pintype "passive"))
      (node (ref "S248") (pin "2") (pinfunction "2_2") (pintype "passive"))
      (node (ref "S287") (pin "2") (pinfunction "2_2") (pintype "passive"))
    )
    (net (code "16") (name "/col16") (class "Default")
      (node (ref "S215") (pin "2") (pinfunction "2_2") (pintype "passive"))
      (node (ref "S232") (pin "2") (pinfunction "2_2") (pintype "passive"))
      (node (ref "S249") (pin "2") (pinfunction "2_2") (pintype "passive"))
      (node (ref "S279") (pin "2") (pinfunction "2_2") (pintype "passive"))
      (node (ref "S288") (pin "2") (pinfunction "2_2") (pintype "passive"))
    )
    (net (code "17") (name "/col17") (class "Default")
      (node (ref "S216") (pin "2") (pinfunction "2_2") (pintype "passive"))
      (node (ref "S233") (pin "2") (pinfunction "2_2") (pintype "passive"))
      (node (ref "S250") (pin "2") (pinfunction "2_2") (pintype "passive"))
      (node (ref "S289") (pin "2") (pinfunction "2_2") (pintype "passive"))
    )
    (net (code "18") (name "/row1") (class "Default")
      (node (ref "D201") (pin "2") (pinfunction "K_2") (pintype "passive"))
      (node (ref "D202") (pin "2") (pinfunction "K_2") (pintype "passive"))
      (node (ref "D203") (pin "2") (pinfunction "K_2") (pintype "passive"))
      (node (ref "D204") (pin "2") (pinfunction "K_2") (pintype "passive"))
      (node (ref "D205") (pin "2") (pinfunction "K_2") (pintype "passive"))
      (node (ref "D206") (pin "2") (pinfunction "K_2") (pintype "passive"))
      (node (ref "D207") (pin "2") (pinfunction "K_2") (pintype "passive"))
      (node (ref "D208") (pin "2") (pinfunction "K_2") (pintype "passive"))
      (node (ref "D209") (pin "2") (pinfunction "K_2") (pintype "passive"))
      (node (ref "D210") (pin "2") (pinfunction "K_2") (pintype "passive"))
      (node (ref "D211") (pin "2") (pinfunction "K_2") (pintype "passive"))
      (node (ref "D212") (pin "2") (pinfunction "K_2") (pintype "passive"))
      (node (ref "D213") (pin "2") (pinfunction "K_2") (pintype "passive"))
      (node (ref "D214") (pin "2") (pinfunction "K_2") (pintype "passive"))
      (node (ref "D215") (pin "2") (pinfunction "K_2") (pintype "passive"))
      (node (ref "D216") (pin "2") (pinfunction "K_2") (pintype "passive"))
    )
    (net (code "19") (name "/row2") (class "Default")
      (node (ref "D217") (pin "2") (pinfunction "K_2") (pintype "passive"))
      (node (ref "D218") (pin "2") (pinfunction "K_2") (pintype "passive"))
      (node (ref "D219") (pin "2") (pinfunction "K_2") (pintype "passive"))
      (node (ref "D220") (pin "2") (pinfunction "K_2") (pintype "passive"))
      (node (ref "D221") (pin "2") (pinfunction "K_2") (pintype "passive"))
      (node (ref "D222") (pin "2") (pinfunction "K_2") (pintype "passive"))
      (node (ref "D223") (pin "2") (pinfunction "K_2") (pintype "passive"))
      (node (ref "D224") (pin "2") (pinfunction "K_2") (pintype "passive"))
      (node (ref "D225") (pin "2") (pinfunction "K_2") (pintype "passive"))
      (node (ref "D226") (pin "2") (pinfunction "K_2") (pintype "passive"))
      (node (ref "D227") (pin "2") (pinfunction "K_2") (pintype "passive"))
      (node (ref "D228") (pin "2") (pinfunction "K_2") (pintype "passive"))
      (node (ref "D229") (pin "2") (pinfunction "K_2") (pintype "passive"))
      (node (ref "D230") (pin "2") (pinfunction "K_2") (pintype "passive"))
      (node (ref "D231") (pin "2") (pinfunction "K_2") (pintype "passive"))
      (node (ref "D232") (pin "2") (pinfunction "K_2") (pintype "passive"))
      (node (ref "D233") (pin "2") (pinfunction "K_2") (pintype "passive"))
    )
    (net (code "20") (name "/row3") (class "Default")
      (node (ref "D234") (pin "2") (pinfunction "K_2") (pintype "passive"))
      (node (ref "D235") (pin "2") (pinfunction "K_2") (pintype "passive"))
      (node (ref "D236") (pin "2") (pinfunction "K_2") (pintype "passive"))
      (node (ref "D237") (pin "2") (pinfunction "K_2") (pintype "passive"))
      (node (ref "D238") (pin "2") (pinfunction "K_2") (pintype "passive"))
      (node (ref "D239") (pin "2") (pinfunction "K_2") (pintype "passive"))
      (node (ref "D240") (pin "2") (pinfunction "K_2") (pintype "passive"))
      (node (ref "D241") (pin "2") (pinfunction "K_2") (pintype "passive"))
      (node (ref "D242") (pin "2") (pinfunction "K_2") (pintype "passive"))
      (node (ref "D243") (pin "2") (pinfunction "K_2") (pintype "passive"))
      (node (ref "D244") (pin "2") (pinfunction "K_2") (pintype "passive"))
      (node (ref "D245") (pin "2") (pinfunction "K_2") (pintype "passive"))
      (node (ref "D246") (pin "2") (pinfunction "K_2") (pintype "passive"))
      (node (ref "D247") (pin "2") (pinfunction "K_2") (pintype "passive"))
      (node (ref "D248") (pin "2") (pinfunction "K_2") (pintype "passive"))
      (node (ref "D249") (pin "2") (pinfunction "K_2") (pintype "passive"))
      (node (ref "D250") (pin "2") (pinfunction "K_2") (pintype "passive"))
    )
    (net (code "21") (name "/row4") (class "Default")
      (node (ref "D251") (pin "2") (pinfunction "K_2") (pintype "passive"))
      (node (ref "D252") (pin "2") (pinfunction "K_2") (pintype "passive"))
      (node (ref "D253") (pin "2") (pinfunction "K_2") (pintype "passive"))
      (node (ref "D254") (pin "2") (pinfunction "K_2") (pintype "passive"))
      (node (ref "D255") (pin "2") (pinfunction "K_2") (pintype "passive"))
      (node (ref "D256") (pin "2") (pinfunction "K_2") (pintype "passive"))
      (node (ref "D257") (pin "2") (pinfunction "K_2") (pintype "passive"))
      (node (ref "D258") (pin "2") (pinfunction "K_2") (pintype "passive"))
      (node (ref "D259") (pin "2") (pinfunction "K_2") (pintype "passive"))
      (node (ref "D260") (pin "2") (pinfunction "K_2") (pintype "passive"))
      (node (ref "D261") (pin "2") (pinfunction "K_2") (pintype "passive"))
      (node (ref "D262") (pin "2") (pinfunction "K_2") (pintype "passive"))
      (node (ref "D263") (pin "2") (pinfunction "K_2") (pintype "passive"))
      (node (ref "D264") (pin "2") (pinfunction "K_2") (pintype "passive"))
    )
    (net (code "22") (name "/row5") (class "Default")
      (node (ref "D265") (pin "2") (pinfunction "K_2") (pintype "passive"))
      (node (ref "D266") (pin "2") (pinfunction "K_2") (pintype "passive"))
      (node (ref "D267") (pin "2") (pinfunction "K_2") (pintype "passive"))
      (node (ref "D268") (pin "2") (pinfunction "K_2") (pintype "passive"))
      (node (ref "D269") (pin "2") (pinfunction "K_2") (pintype "passive"))
      (node (ref "D270") (pin "2") (pinfunction "K_2") (pintype "passive"))
      (node (ref "D271") (pin "2") (pinfunction "K_2") (pintype "passive"))
      (node (ref "D272") (pin "2") (pinfunction "K_2") (pintype "passive"))
      (node (ref "D273") (pin "2") (pinfunction "K_2") (pintype "passive"))
      (node (ref "D274") (pin "2") (pinfunction "K_2") (pintype "passive"))
      (node (ref "D275") (pin "2") (pinfunction "K_2") (pintype "passive"))
      (node (ref "D276") (pin "2") (pinfunction "K_2") (pintype "passive"))
      (node (ref "D277") (pin "2") (pinfunction "K_2") (pintype "passive"))
      (node (ref "D278") (pin "2") (pinfunction "K_2") (pintype "passive"))
      (node (ref "D279") (pin "2") (pinfunction "K_2") (pintype "passive"))
    )
    (net (code "23") (name "/row6") (class "Default")
      (node (ref "D280") (pin "2") (pinfunction "K_2") (pintype "passive"))
      (node (ref "D281") (pin "2") (pinfunction "K_2") (pintype "passive"))
      (node (ref "D282") (pin "2") (pinfunction "K_2") (pintype "passive"))
      (node (ref "D283") (pin "2") (pinfunction "K_2") (pintype "passive"))
      (node (ref "D284") (pin "2") (pinfunction "K_2") (pintype "passive"))
      (node (ref "D285") (pin "2") (pinfunction "K_2") (pintype "passive"))
      (node (ref "D286") (pin "2") (pinfunction "K_2") (pintype "passive"))
      (node (ref "D287") (pin "2") (pinfunction "K_2") (pintype "passive"))
      (node (ref "D288") (pin "2") (pinfunction "K_2") (pintype "passive"))
      (node (ref "D289") (pin "2") (pinfunction "K_2") (pintype "passive"))
    )
    (net (code "24") (name "Net-(D201-A)") (class "Default")
      (node (ref "D201") (pin "1") (pinfunction "A_1") (pintype "passive"))
      (node (ref "S201") (pin "1") (pinfunction "1_1") (pintype "passive"))
    )
    (net (code "25") (name "Net-(D202-A)") (class "Default")
      (node (ref "D202") (pin "1") (pinfunction "A_1") (pintype "passive"))
      (node (ref "S202") (pin "1") (pinfunction "1_1") (pintype "passive"))
    )
    (net (code "26") (name "Net-(D203-A)") (class "Default")
      (node (ref "D203") (pin "1") (pinfunction "A_1") (pintype "passive"))
      (node (ref "S203") (pin "1") (pinfunction "1_1") (pintype "passive"))
    )
    (net (code "27") (name "Net-(D204-A)") (class "Default")
      (node (ref "D204") (pin "1") (pinfunction "A_1") (pintype "passive"))
      (node (ref "S204") (pin "1") (pinfunction "1_1") (pintype "passive"))
    )
    (net (code "28") (name "Net-(D205-A)") (class "Default")
      (node (ref "D205") (pin "1") (pinfunction "A_1") (pintype "passive"))
      (node (ref "S205") (pin "1") (pinfunction "1_1") (pintype "passive"))
    )
    (net (code "29") (name "Net-(D206-A)") (class "Default")
      (node (ref "D206") (pin "1") (pinfunction "A_1") (pintype "passive"))
      (node (ref "S206") (pin "1") (pinfunction "1_1") (pintype "passive"))
    )
    (net (code "30") (name "Net-(D207-A)") (class "Default")
      (node (ref "D207") (pin "1") (pinfunction "A_1") (pintype "passive"))
      (node (ref "S207") (pin "1") (pinfunction "1_1") (pintype "passive"))
    )
    (net (code "31") (name "Net-(D208-A)") (class "Default")
      (node (ref "D208") (pin "1") (pinfunction "A_1") (pintype "passive"))
      (node (ref "S208") (pin "1") (pinfunction "1_1") (pintype "passive"))
    )
    (net (code "32") (name "Net-(D209-A)") (class "Default")
      (node (ref "D209") (pin "1") (pinfunction "A_1") (pintype "passive"))
      (node (ref "S209") (pin "1") (pinfunction "1_1") (pintype "passive"))
    )
    (net (code "33") (name "Net-(D210-A)") (class "Default")
      (node (ref "D210") (pin "1") (pinfunction "A_1") (pintype "passive"))
      (node (ref "S210") (pin "1") (pinfunction "1_1") (pintype "passive"))
    )
    (net (code "34") (name "Net-(D211-A)") (class "Default")
      (node (ref "D211") (pin "1") (pinfunction "A_1") (pintype "passive"))
      (node (ref "S211") (pin "1") (pinfunction "1_1") (pintype "passive"))
    )
    (net (code "35") (name "Net-(D212-A)") (class "Default")
      (node (ref "D212") (pin "1") (pinfunction "A_1") (pintype "passive"))
      (node (ref "S212") (pin "1") (pinfunction "1_1") (pintype "passive"))
    )
    (net (code "36") (name "Net-(D213-A)") (class "Default")
      (node (ref "D213") (pin "1") (pinfunction "A_1") (pintype "passive"))
      (node (ref "S213") (pin "1") (pinfunction "1_1") (pintype "passive"))
    )
    (net (code "37") (name "Net-(D214-A)") (class "Default")
      (node (ref "D214") (pin "1") (pinfunction "A_1") (pintype "passive"))
      (node (ref "S214") (pin "1") (pinfunction "1_1") (pintype "passive"))
    )
    (net (code "38") (name "Net-(D215-A)") (class "Default")
      (node (ref "D215") (pin "1") (pinfunction "A_1") (pintype "passive"))
      (node (ref "S215") (pin "1") (pinfunction "1_1") (pintype "passive"))
    )
    (net (code "39") (name "Net-(D216-A)") (class "Default")
      (node (ref "D216") (pin "1") (pinfunction "A_1") (pintype "passive"))
      (node (ref "S216") (pin "1") (pinfunction "1_1") (pintype "passive"))
    )
    (net (code "40") (name "Net-(D217-A)") (class "Default")
      (node (ref "D217") (pin "1") (pinfunction "A_1") (pintype "passive"))
      (node (ref "S217") (pin "1") (pinfunction "1_1") (pintype "passive"))
    )
    (net (code "41") (name "Net-(D218-A)") (class "Default")
      (node (ref "D218") (pin "1") (pinfunction "A_1") (pintype "passive"))
      (node (ref "S218") (pin "1") (pinfunction "1_1") (pintype "passive"))
    )
    (net (code "42") (name "Net-(D219-A)") (class "Default")
      (node (ref "D219") (pin "1") (pinfunction "A_1") (pintype "passive"))
      (node (ref "S219") (pin "1") (pinfunction "1_1") (pintype "passive"))
    )
    (net (code "43") (name "Net-(D220-A)") (class "Default")
      (node (ref "D220") (pin "1") (pinfunction "A_1") (pintype "passive"))
      (node (ref "S220") (pin "1") (pinfunction "1_1") (pintype "passive"))
    )
    (net (code "44") (name "Net-(D221-A)") (class "Default")
      (node (ref "D221") (pin "1") (pinfunction "A_1") (pintype "passive"))
      (node (ref "S221") (pin "1") (pinfunction "1_1") (pintype "passive"))
    )
    (net (code "45") (name "Net-(D222-A)") (class "Default")
      (node (ref "D222") (pin "1") (pinfunction "A_1") (pintype "passive"))
      (node (ref "S222") (pin "1") (pinfunction "1_1") (pintype "passive"))
    )
    (net (code "46") (name "Net-(D223-A)") (class "Default")
      (node (ref "D223") (pin "1") (pinfunction "A_1") (pintype "passive"))
      (node (ref "S223") (pin "1") (pinfunction "1_1") (pintype "passive"))
    )
    (net (code "47") (name "Net-(D224-A)") (class "Default")
      (node (ref "D224") (pin "1") (pinfunction "A_1") (pintype "passive"))
      (node (ref "S224") (pin "1") (pinfunction "1_1") (pintype "passive"))
    )
    (net (code "48") (name "Net-(D225-A)") (class "Default")
      (node (ref "D225") (pin "1") (pinfunction "A_1") (pintype "passive"))
      (node (ref "S225") (pin "1") (pinfunction "1_1") (pintype "passive"))
    )
    (net (code "49") (name "Net-(D226-A)") (class "Default")
      (node (ref "D226") (pin "1") (pinfunction "A_1") (pintype "passive"))
      (node (ref "S226") (pin "1") (pinfunction "1_1") (pintype "passive"))
    )
    (net (code "50") (name "Net-(D227-A)") (class "Default")
      (node (ref "D227") (pin "1") (pinfunction "A_1") (pintype "passive"))
      (node (ref "S227") (pin "1") (pinfunction "1_1") (pintype "passive"))
    )
    (net (code "51") (name "Net-(D228-A)") (class "Default")
      (node (ref "D228") (pin "1") (pinfunction "A_1") (pintype "passive"))
      (node (ref "S228") (pin "1") (pinfunction "1_1") (pintype "passive"))
    )
    (net (code "52") (name "Net-(D229-A)") (class "Default")
      (node (ref "D229") (pin "1") (pinfunction "A_1") (pintype "passive"))
      (node (ref "S229") (pin "1") (pinfunction "1_1") (pintype "passive"))
    )
    (net (code "53") (name "Net-(D230-A)") (class "Default")
      (node (ref "D230") (pin "1") (pinfunction "A_1") (pintype "passive"))
      (node (ref "S230") (pin "1") (pinfunction "1_1") (pintype "passive"))
    )
    (net (code "54") (name "Net-(D231-A)") (class "Default")
      (node (ref "D231") (pin "1") (pinfunction "A_1") (pintype "passive"))
      (node (ref "S231") (pin "1") (pinfunction "1_1") (pintype "passive"))
    )
    (net (code "55") (name "Net-(D232-A)") (class "Default")
      (node (ref "D232") (pin "1") (pinfunction "A_1") (pintype "passive"))
      (node (ref "S232") (pin "1") (pinfunction "1_1") (pintype "passive"))
    )
    (net (code "56") (name "Net-(D233-A)") (class "Default")
      (node (ref "D233") (pin "1") (pinfunction "A_1") (pintype "passive"))
      (node (ref "S233") (pin "1") (pinfunction "1_1") (pintype "passive"))
    )
    (net (code "57") (name "Net-(D234-A)") (class "Default")
      (node (ref "D234") (pin "1") (pinfunction "A_1") (pintype "passive"))
      (node (ref "S234") (pin "1") (pinfunction "1_1") (pintype "passive"))
    )
    (net (code "58") (name "Net-(D235-A)") (class "Default")
      (node (ref "D235") (pin "1") (pinfunction "A_1") (pintype "passive"))
      (node (ref "S235") (pin "1") (pinfunction "1_1") (pintype "passive"))
    )
    (net (code "59") (name "Net-(D236-A)") (class "Default")
      (node (ref "D236") (pin "1") (pinfunction "A_1") (pintype "passive"))
      (node (ref "S236") (pin "1") (pinfunction "1_1") (pintype "passive"))
    )
    (net (code "60") (name "Net-(D237-A)") (class "Default")
      (node (ref "D237") (pin "1") (pinfunction "A_1") (pintype "passive"))
      (node (ref "S237") (pin "1") (pinfunction "1_1") (pintype "passive"))
    )
    (net (code "61") (name "Net-(D238-A)") (class "Default")
      (node (ref "D238") (pin "1") (pinfunction "A_1") (pintype "passive"))
      (node (ref "S238") (pin "1") (pinfunction "1_1") (pintype "passive"))
    )
    (net (code "62") (name "Net-(D239-A)") (class "Default")
      (node (ref "D239") (pin "1") (pinfunction "A_1") (pintype "passive"))
      (node (ref "S239") (pin "1") (pinfunction "1_1") (pintype "passive"))
    )
    (net (code "63") (name "Net-(D240-A)") (class "Default")
      (node (ref "D240") (pin "1") (pinfunction "A_1") (pintype "passive"))
      (node (ref "S240") (pin "1") (pinfunction "1_1") (pintype "passive"))
    )
    (net (code "64") (name "Net-(D241-A)") (class "Default")
      (node (ref "D241") (pin "1") (pinfunction "A_1") (pintype "passive"))
      (node (ref "S241") (pin "1") (pinfunction "1_1") (pintype "passive"))
    )
    (net (code "65") (name "Net-(D242-A)") (class "Default")
      (node (ref "D242") (pin "1") (pinfunction "A_1") (pintype "passive"))
      (node (ref "S242") (pin "1") (pinfunction "1_1") (pintype "passive"))
    )
    (net (code "66") (name "Net-(D243-A)") (class "Default")
      (node (ref "D243") (pin "1") (pinfunction "A_1") (pintype "passive"))
      (node (ref "S243") (pin "1") (pinfunction "1_1") (pintype "passive"))
    )
    (net (code "67") (name "Net-(D244-A)") (class "Default")
      (node (ref "D244") (pin "1") (pinfunction "A_1") (pintype "passive"))
      (node (ref "S244") (pin "1") (pinfunction "1_1") (pintype "passive"))
    )
    (net (code "68") (name "Net-(D245-A)") (class "Default")
      (node (ref "D245") (pin "1") (pinfunction "A_1") (pintype "passive"))
      (node (ref "S245") (pin "1") (pinfunction "1_1") (pintype "passive"))
    )
    (net (code "69") (name "Net-(D246-A)") (class "Default")
      (node (ref "D246") (pin "1") (pinfunction "A_1") (pintype "passive"))
      (node (ref "S246") (pin "1") (pinfunction "1_1") (pintype "passive"))
    )
    (net (code "70") (name "Net-(D247-A)") (class "Default")
      (node (ref "D247") (pin "1") (pinfunction "A_1") (pintype "passive"))
      (node (ref "S247") (pin "1") (pinfunction "1_1") (pintype "passive"))
    )
    (net (code "71") (name "Net-(D248-A)") (class "Default")
      (node (ref "D248") (pin "1") (pinfunction "A_1") (pintype "passive"))
      (node (ref "S248") (pin "1") (pinfunction "1_1") (pintype "passive"))
    )
    (net (code "72") (name "Net-(D249-A)") (class "Default")
      (node (ref "D249") (pin "1") (pinfunction "A_1") (pintype "passive"))
      (node (ref "S249") (pin "1") (pinfunction "1_1") (pintype "passive"))
    )
    (net (code "73") (name "Net-(D250-A)") (class "Default")
      (node (ref "D250") (pin "1") (pinfunction "A_1") (pintype "passive"))
      (node (ref "S250") (pin "1") (pinfunction "1_1") (pintype "passive"))
    )
    (net (code "74") (name "Net-(D251-A)") (class "Default")
      (node (ref "D251") (pin "1") (pinfunction "A_1") (pintype "passive"))
      (node (ref "S251") (pin "1") (pinfunction "1_1") (pintype "passive"))
    )
    (net (code "75") (name "Net-(D252-A)") (class "Default")
      (node (ref "D252") (pin "1") (pinfunction "A_1") (pintype "passive"))
      (node (ref "S252") (pin "1") (pinfunction "1_1") (pintype "passive"))
    )
    (net (code "76") (name "Net-(D253-A)") (class "Default")
      (node (ref "D253") (pin "1") (pinfunction "A_1") (pintype "passive"))
      (node (ref "S253") (pin "1") (pinfunction "1_1") (pintype "passive"))
    )
    (net (code "77") (name "Net-(D254-A)") (class "Default")
      (node (ref "D254") (pin "1") (pinfunction "A_1") (pintype "passive"))
      (node (ref "S254") (pin "1") (pinfunction "1_1") (pintype "passive"))
    )
    (net (code "78") (name "Net-(D255-A)") (class "Default")
      (node (ref "D255") (pin "1") (pinfunction "A_1") (pintype "passive"))
      (node (ref "S255") (pin "1") (pinfunction "1_1") (pintype "passive"))
    )
    (net (code "79") (name "Net-(D256-A)") (class "Default")
      (node (ref "D256") (pin "1") (pinfunction "A_1") (pintype "passive"))
      (node (ref "S256") (pin "1") (pinfunction "1_1") (pintype "passive"))
    )
    (net (code "80") (name "Net-(D257-A)") (class "Default")
      (node (ref "D257") (pin "1") (pinfunction "A_1") (pintype "passive"))
      (node (ref "S257") (pin "1") (pinfunction "1_1") (pintype "passive"))
    )
    (net (code "81") (name "Net-(D258-A)") (class "Default")
      (node (ref "D258") (pin "1") (pinfunction "A_1") (pintype "passive"))
      (node (ref "S258") (pin "1") (pinfunction "1_1") (pintype "passive"))
    )
    (net (code "82") (name "Net-(D259-A)") (class "Default")
      (node (ref "D259") (pin "1") (pinfunction "A_1") (pintype "passive"))
      (node (ref "S259") (pin "1") (pinfunction "1_1") (pintype "passive"))
    )
    (net (code "83") (name "Net-(D260-A)") (class "Default")
      (node (ref "D260") (pin "1") (pinfunction "A_1") (pintype "passive"))
      (node (ref "S260") (pin "1") (pinfunction "1_1") (pintype "passive"))
    )
    (net (code "84") (name "Net-(D261-A)") (class "Default")
      (node (ref "D261") (pin "1") (pinfunction "A_1") (pintype "passive"))
      (node (ref "S261") (pin "1") (pinfunction "1_1") (pintype "passive"))
    )
    (net (code "85") (name "Net-(D262-A)") (class "Default")
      (node (ref "D262") (pin "1") (pinfunction "A_1") (pintype "passive"))
      (node (ref "S262") (pin "1") (pinfunction "1_1") (pintype "passive"))
    )
    (net (code "86") (name "Net-(D263-A)") (class "Default")
      (node (ref "D263") (pin "1") (pinfunction "A_1") (pintype "passive"))
      (node (ref "S263") (pin "1") (pinfunction "1_1") (pintype "passive"))
    )
    (net (code "87") (name "Net-(D264-A)") (class "Default")
      (node (ref "D264") (pin "1") (pinfunction "A_1") (pintype "passive"))
      (node (ref "S264") (pin "1") (pinfunction "1_1") (pintype "passive"))
      (node (ref "S264_1") (pin "1") (pinfunction "1_1") (pintype "passive"))
    )
    (net (code "88") (name "Net-(D265-A)") (class "Default")
      (node (ref "D265") (pin "1") (pinfunction "A_1") (pintype "passive"))
      (node (ref "S265") (pin "1") (pinfunction "1_1") (pintype "passive"))
    )
    (net (code "89") (name "Net-(D266-A)") (class "Default")
      (node (ref "D266") (pin "1") (pinfunction "A_1") (pintype "passive"))
      (node (ref "S266") (pin "1") (pinfunction "1_1") (pintype "passive"))
    )
    (net (code "90") (name "Net-(D267-A)") (class "Default")
      (node (ref "D267") (pin "1") (pinfunction "A_1") (pintype "passive"))
      (node (ref "S267") (pin "1") (pinfunction "1_1") (pintype "passive"))
    )
    (net (code "91") (name "Net-(D268-A)") (class "Default")
      (node (ref "D268") (pin "1") (pinfunction "A_1") (pintype "passive"))
      (node (ref "S268") (pin "1") (pinfunction "1_1") (pintype "passive"))
    )
    (net (code "92") (name "Net-(D269-A)") (class "Default")
      (node (ref "D269") (pin "1") (pinfunction "A_1") (pintype "passive"))
      (node (ref "S269") (pin "1") (pinfunction "1_1") (pintype "passive"))
    )
    (net (code "93") (name "Net-(D270-A)") (class "Default")
      (node (ref "D270") (pin "1") (pinfunction "A_1") (pintype "passive"))
      (node (ref "S270") (pin "1") (pinfunction "1_1") (pintype "passive"))
    )
    (net (code "94") (name "Net-(D271-A)") (class "Default")
      (node (ref "D271") (pin "1") (pinfunction "A_1") (pintype "passive"))
      (node (ref "S271") (pin "1") (pinfunction "1_1") (pintype "passive"))
    )
    (net (code "95") (name "Net-(D272-A)") (class "Default")
      (node (ref "D272") (pin "1") (pinfunction "A_1") (pintype "passive"))
      (node (ref "S272") (pin "1") (pinfunction "1_1") (pintype "passive"))
    )
    (net (code "96") (name "Net-(D273-A)") (class "Default")
      (node (ref "D273") (pin "1") (pinfunction "A_1") (pintype "passive"))
      (node (ref "S273") (pin "1") (pinfunction "1_1") (pintype "passive"))
    )
    (net (code "97") (name "Net-(D274-A)") (class "Default")
      (node (ref "D274") (pin "1") (pinfunction "A_1") (pintype "passive"))
      (node (ref "S274") (pin "1") (pinfunction "1_1") (pintype "passive"))
    )
    (net (code "98") (name "Net-(D275-A)") (class "Default")
      (node (ref "D275") (pin "1") (pinfunction "A_1") (pintype "passive"))
      (node (ref "S275") (pin "1") (pinfunction "1_1") (pintype "passive"))
    )
    (net (code "99") (name "Net-(D276-A)") (class "Default")
      (node (ref "D276") (pin "1") (pinfunction "A_1") (pintype "passive"))
      (node (ref "S276") (pin "1") (pinfunction "1_1") (pintype "passive"))
    )
    (net (code "100") (name "Net-(D277-A)") (class "Default")
      (node (ref "D277") (pin "1") (pinfunction "A_1") (pintype "passive"))
      (node (ref "S277") (pin "1") (pinfunction "1_1") (pintype "passive"))
    )
    (net (code "101") (name "Net-(D278-A)") (class "Default")
      (node (ref "D278") (pin "1") (pinfunction "A_1") (pintype "passive"))
      (node (ref "S278") (pin "1") (pinfunction "1_1") (pintype "passive"))
    )
    (net (code "102") (name "Net-(D279-A)") (class "Default")
      (node (ref "D279") (pin "1") (pinfunction "A_1") (pintype "passive"))
      (node (ref "S279") (pin "1") (pinfunction "1_1") (pintype "passive"))
    )
    (net (code "103") (name "Net-(D280-A)") (class "Default")
      (node (ref "D280") (pin "1") (pinfunction "A_1") (pintype "passive"))
      (node (ref "S280") (pin "1") (pinfunction "1_1") (pintype "passive"))
    )
    (net (code "104") (name "Net-(D281-A)") (class "Default")
      (node (ref "D281") (pin "1") (pinfunction "A_1") (pintype "passive"))
      (node (ref "S281") (pin "1") (pinfunction "1_1") (pintype "passive"))
    )
    (net (code "105") (name "Net-(D282-A)") (class "Default")
      (node (ref "D282") (pin "1") (pinfunction "A_1") (pintype "passive"))
      (node (ref "S282") (pin "1") (pinfunction "1_1") (pintype "passive"))
    )
    (net (code "106") (name "Net-(D283-A)") (class "Default")
      (node (ref "D283") (pin "1") (pinfunction "A_1") (pintype "passive"))
      (node (ref "S283") (pin "1") (pinfunction "1_1") (pintype "passive"))
    )
    (net (code "107") (name "Net-(D284-A)") (class "Default")
      (node (ref "D284") (pin "1") (pinfunction "A_1") (pintype "passive"))
      (node (ref "S284") (pin "1") (pinfunction "1_1") (pintype "passive"))
    )
    (net (code "108") (name "Net-(D285-A)") (class "Default")
      (node (ref "D285") (pin "1") (pinfunction "A_1") (pintype "passive"))
      (node (ref "S285") (pin "1") (pinfunction "1_1") (pintype "passive"))
    )
    (net (code "109") (name "Net-(D286-A)") (class "Default")
      (node (ref "D286") (pin "1") (pinfunction "A_1") (pintype "passive"))
      (node (ref "S286") (pin "1") (pinfunction "1_1") (pintype "passive"))
    )
    (net (code "110") (name "Net-(D287-A)") (class "Default")
      (node (ref "D287") (pin "1") (pinfunction "A_1") (pintype "passive"))
      (node (ref "S287") (pin "1") (pinfunction "1_1") (pintype "passive"))
    )
    (net (code "111") (name "Net-(D288-A)") (class "Default")
      (node (ref "D288") (pin "1") (pinfunction "A_1") (pintype "passive"))
      (node (ref "S288") (pin "1") (pinfunction "1_1") (pintype "passive"))
    )
    (net (code "112") (name "Net-(D289-A)") (class "Default")
      (node (ref "D289") (pin "1") (pinfunction "A_1") (pintype "passive"))
      (node (ref "S289") (pin "1") (pinfunction "1_1") (pintype "passive"))
    )
  )
)
